# music_visualizer.net
KiCad netlist of a schematic drawn in EAGLE
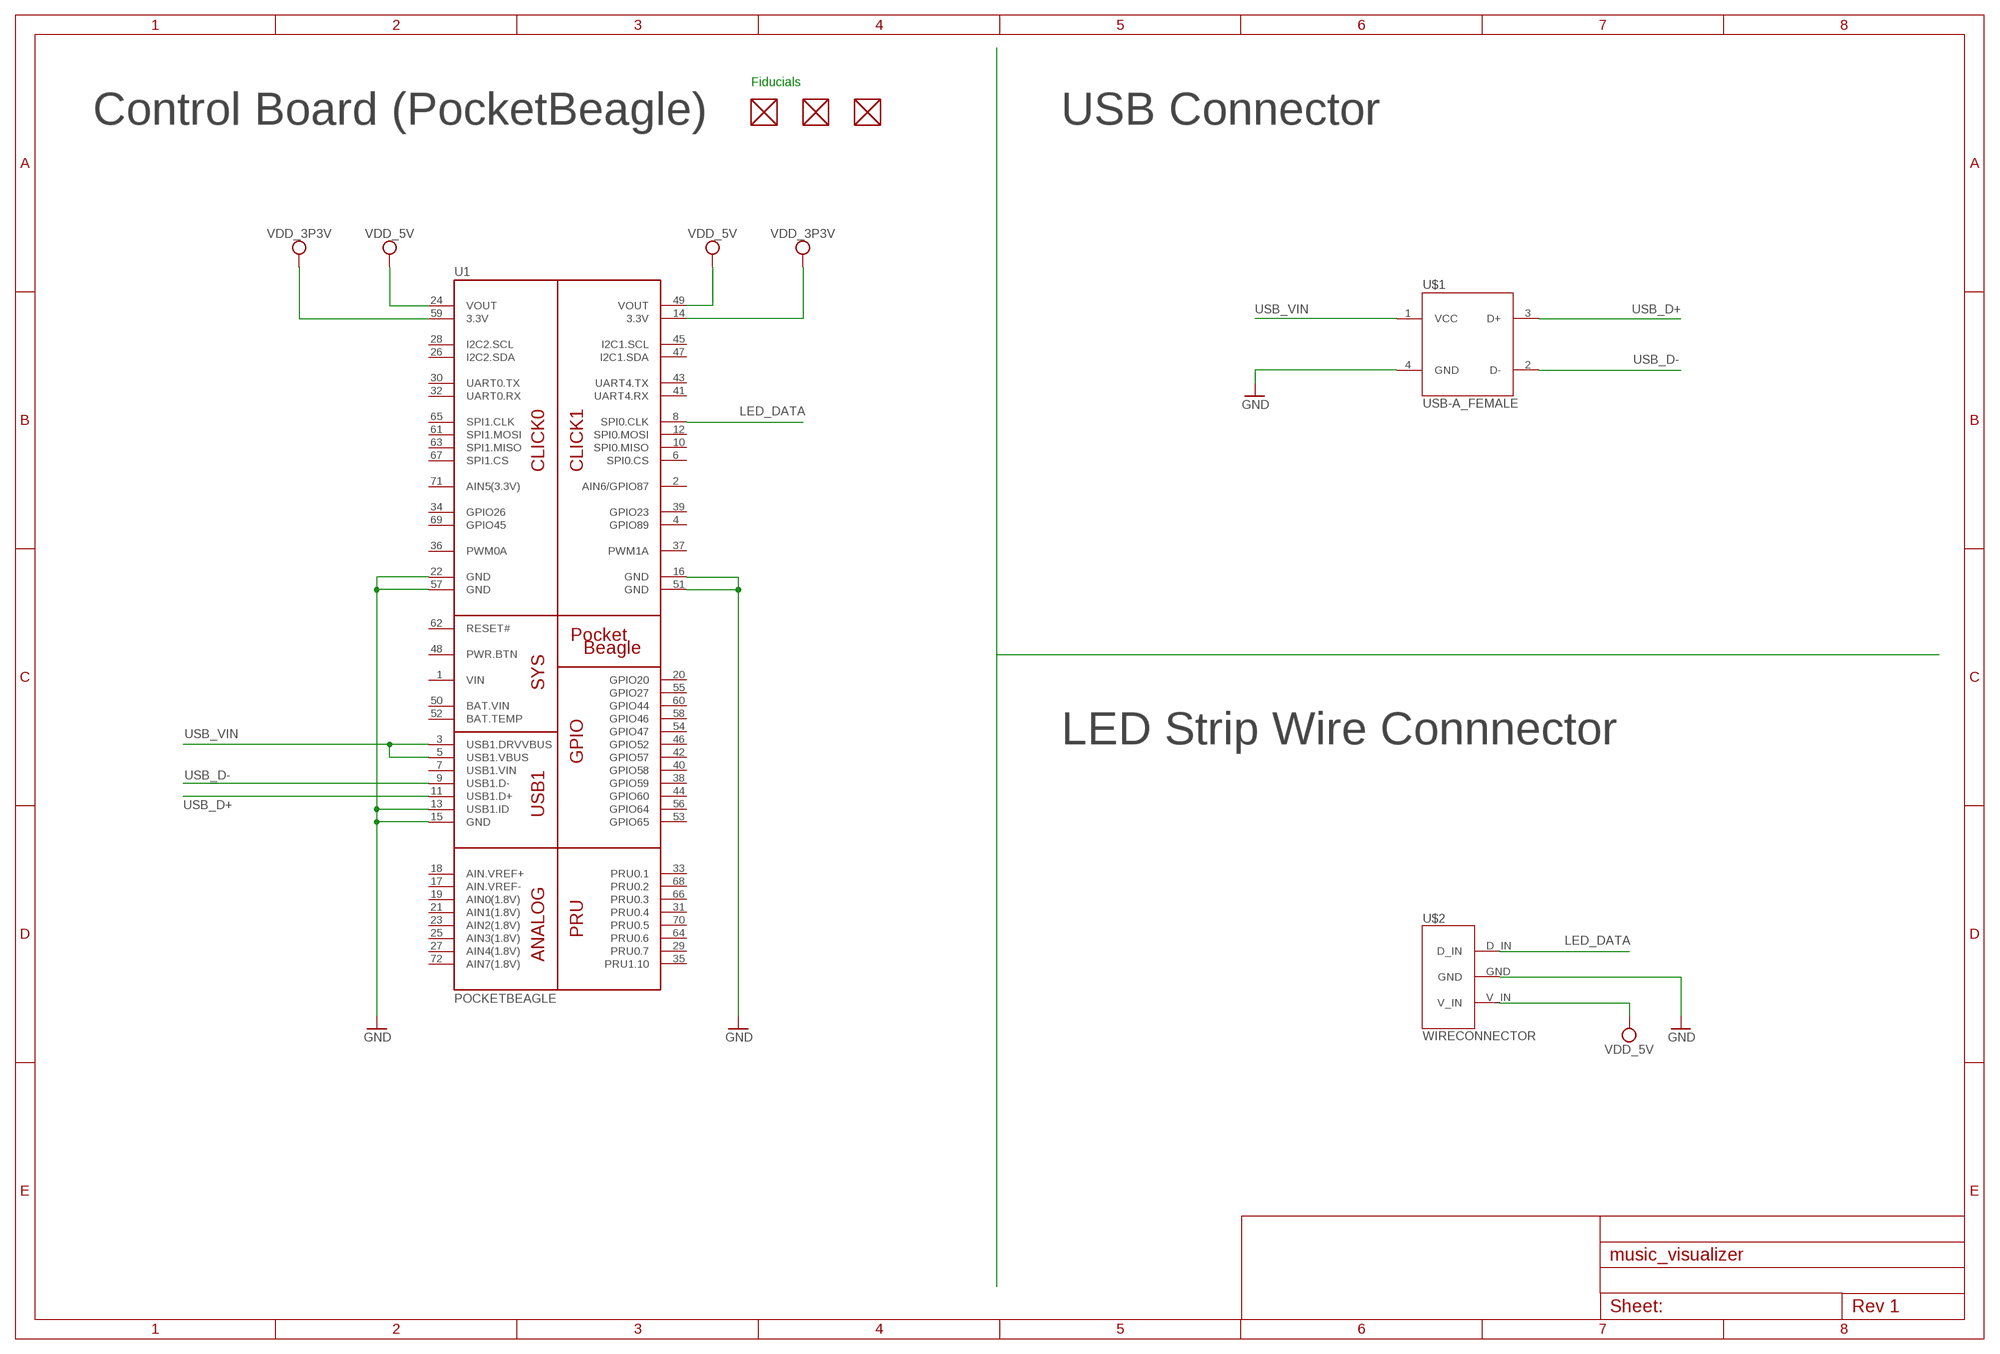
[diagram p0: schematic, sheet 1]

(export (version "E")
  (design (tool "Eeschema 10.0.6"))
  (components
    (comp (ref "FUD1")
      (value "FIDUCIAL")
      (footprint "eagle-import:FIDUCIAL_40MIL")
      (libsource (lib "eagle-import") (part "FIDUCIAL"))
    )
    (comp (ref "FUD2")
      (value "FIDUCIAL")
      (footprint "eagle-import:FIDUCIAL_40MIL")
      (libsource (lib "eagle-import") (part "FIDUCIAL"))
    )
    (comp (ref "FUD3")
      (value "FIDUCIAL")
      (footprint "eagle-import:FIDUCIAL_40MIL")
      (libsource (lib "eagle-import") (part "FIDUCIAL"))
    )
    (comp (ref "U$1")
      (value "USB-A_FEMALE")
      (footprint "eagle-import:USB-A_FEMALE")
      (libsource (lib "eagle-import") (part "USB-A_FEMALE"))
    )
    (comp (ref "U$2")
      (value "WIRECONNECTOR")
      (footprint "eagle-import:WIRECONNECTOR")
      (libsource (lib "eagle-import") (part "WIRECONNECTOR"))
    )
    (comp (ref "U1")
      (value "POCKETBEAGLE")
      (footprint "eagle-import:POCKETBEAGLE")
      (libsource (lib "eagle-import") (part "POCKETBEAGLE"))
    )
  )
  (nets
    (net (code "1") (name "/BAT.VIN") (class "Default")
      (node (ref "U1") (pin "50") (pinfunction "BAT.VIN_50") (pintype "power_in"))
    )
    (net (code "2") (name "/LED_DATA") (class "Default")
      (node (ref "U$2") (pin "D_IN") (pinfunction "D_IN_D_IN") (pintype "bidirectional"))
      (node (ref "U1") (pin "8") (pinfunction "SPI0.CLK_8") (pintype "bidirectional"))
    )
    (net (code "3") (name "/USB_D+") (class "Default")
      (node (ref "U$1") (pin "3") (pinfunction "D+_3") (pintype "bidirectional"))
      (node (ref "U1") (pin "11") (pinfunction "USB1.D+_11") (pintype "bidirectional"))
    )
    (net (code "4") (name "/USB_D-") (class "Default")
      (node (ref "U$1") (pin "2") (pinfunction "D-_2") (pintype "bidirectional"))
      (node (ref "U1") (pin "9") (pinfunction "USB1.D-_9") (pintype "bidirectional"))
    )
    (net (code "5") (name "/USB_VIN") (class "Default")
      (node (ref "U$1") (pin "1") (pinfunction "VCC_1") (pintype "bidirectional"))
      (node (ref "U1") (pin "3") (pinfunction "USB1.DRVVBUS_3") (pintype "bidirectional"))
      (node (ref "U1") (pin "5") (pinfunction "USB1.VBUS_5") (pintype "bidirectional"))
    )
    (net (code "6") (name "/VIN") (class "Default")
      (node (ref "U1") (pin "1") (pinfunction "VIN_1") (pintype "power_in"))
    )
    (net (code "7") (name "GND") (class "Default")
      (node (ref "U$1") (pin "4") (pinfunction "GND_4") (pintype "bidirectional"))
      (node (ref "U$2") (pin "GND") (pinfunction "GND_GND") (pintype "bidirectional"))
      (node (ref "U1") (pin "13") (pinfunction "USB1.ID_13") (pintype "bidirectional"))
      (node (ref "U1") (pin "15") (pinfunction "GND_15") (pintype "bidirectional"))
      (node (ref "U1") (pin "16") (pinfunction "GND_16") (pintype "power_in"))
      (node (ref "U1") (pin "22") (pinfunction "GND_22") (pintype "power_in"))
      (node (ref "U1") (pin "51") (pinfunction "GND_51") (pintype "power_in"))
      (node (ref "U1") (pin "57") (pinfunction "GND_57") (pintype "power_in"))
    )
    (net (code "8") (name "VDD_3P3V") (class "Default")
      (node (ref "U1") (pin "14") (pinfunction "3.3V_14") (pintype "power_in"))
      (node (ref "U1") (pin "59") (pinfunction "3.3V_59") (pintype "power_in"))
    )
    (net (code "9") (name "VDD_5V") (class "Default")
      (node (ref "U$2") (pin "V_IN") (pinfunction "V_IN_V_IN") (pintype "bidirectional"))
      (node (ref "U1") (pin "24") (pinfunction "VOUT_24") (pintype "power_in"))
      (node (ref "U1") (pin "49") (pinfunction "VOUT_49") (pintype "power_in"))
    )
    (net (code "10") (name "unconnected-(FUD1-PadP$1)") (class "Default")
      (node (ref "FUD1") (pin "P$1") (pinfunction "P$1_P$1") (pintype "no_connect"))
    )
    (net (code "11") (name "unconnected-(FUD2-PadP$1)") (class "Default")
      (node (ref "FUD2") (pin "P$1") (pinfunction "P$1_P$1") (pintype "no_connect"))
    )
    (net (code "12") (name "unconnected-(FUD3-PadP$1)") (class "Default")
      (node (ref "FUD3") (pin "P$1") (pinfunction "P$1_P$1") (pintype "no_connect"))
    )
    (net (code "13") (name "unconnected-(U1-AIN.VREF+-Pad18)") (class "Default")
      (node (ref "U1") (pin "18") (pinfunction "AIN.VREF+_18") (pintype "input"))
    )
    (net (code "14") (name "unconnected-(U1-AIN.VREF--Pad17)") (class "Default")
      (node (ref "U1") (pin "17") (pinfunction "AIN.VREF-_17") (pintype "input"))
    )
    (net (code "15") (name "unconnected-(U1-AIN0(1.8V)-Pad19)") (class "Default")
      (node (ref "U1") (pin "19") (pinfunction "AIN0(1.8V)_19") (pintype "input"))
    )
    (net (code "16") (name "unconnected-(U1-AIN1(1.8V)-Pad21)") (class "Default")
      (node (ref "U1") (pin "21") (pinfunction "AIN1(1.8V)_21") (pintype "input"))
    )
    (net (code "17") (name "unconnected-(U1-AIN2(1.8V)-Pad23)") (class "Default")
      (node (ref "U1") (pin "23") (pinfunction "AIN2(1.8V)_23") (pintype "input"))
    )
    (net (code "18") (name "unconnected-(U1-AIN3(1.8V)-Pad25)") (class "Default")
      (node (ref "U1") (pin "25") (pinfunction "AIN3(1.8V)_25") (pintype "input"))
    )
    (net (code "19") (name "unconnected-(U1-AIN4(1.8V)-Pad27)") (class "Default")
      (node (ref "U1") (pin "27") (pinfunction "AIN4(1.8V)_27") (pintype "input"))
    )
    (net (code "20") (name "unconnected-(U1-AIN5(3.3V)-Pad71)") (class "Default")
      (node (ref "U1") (pin "71") (pinfunction "AIN5(3.3V)_71") (pintype "bidirectional"))
    )
    (net (code "21") (name "unconnected-(U1-AIN6{slash}GPIO87-Pad2)") (class "Default")
      (node (ref "U1") (pin "2") (pinfunction "AIN6/GPIO87_2") (pintype "bidirectional"))
    )
    (net (code "22") (name "unconnected-(U1-AIN7(1.8V)-Pad72)") (class "Default")
      (node (ref "U1") (pin "72") (pinfunction "AIN7(1.8V)_72") (pintype "input"))
    )
    (net (code "23") (name "unconnected-(U1-BAT.TEMP-Pad52)") (class "Default")
      (node (ref "U1") (pin "52") (pinfunction "BAT.TEMP_52") (pintype "input"))
    )
    (net (code "24") (name "unconnected-(U1-GPIO20-Pad20)") (class "Default")
      (node (ref "U1") (pin "20") (pinfunction "GPIO20_20") (pintype "bidirectional"))
    )
    (net (code "25") (name "unconnected-(U1-GPIO23-Pad39)") (class "Default")
      (node (ref "U1") (pin "39") (pinfunction "GPIO23_39") (pintype "bidirectional"))
    )
    (net (code "26") (name "unconnected-(U1-GPIO26-Pad34)") (class "Default")
      (node (ref "U1") (pin "34") (pinfunction "GPIO26_34") (pintype "bidirectional"))
    )
    (net (code "27") (name "unconnected-(U1-GPIO27-Pad55)") (class "Default")
      (node (ref "U1") (pin "55") (pinfunction "GPIO27_55") (pintype "bidirectional"))
    )
    (net (code "28") (name "unconnected-(U1-GPIO44-Pad60)") (class "Default")
      (node (ref "U1") (pin "60") (pinfunction "GPIO44_60") (pintype "bidirectional"))
    )
    (net (code "29") (name "unconnected-(U1-GPIO45-Pad69)") (class "Default")
      (node (ref "U1") (pin "69") (pinfunction "GPIO45_69") (pintype "bidirectional"))
    )
    (net (code "30") (name "unconnected-(U1-GPIO46-Pad58)") (class "Default")
      (node (ref "U1") (pin "58") (pinfunction "GPIO46_58") (pintype "bidirectional"))
    )
    (net (code "31") (name "unconnected-(U1-GPIO47-Pad54)") (class "Default")
      (node (ref "U1") (pin "54") (pinfunction "GPIO47_54") (pintype "bidirectional"))
    )
    (net (code "32") (name "unconnected-(U1-GPIO52-Pad46)") (class "Default")
      (node (ref "U1") (pin "46") (pinfunction "GPIO52_46") (pintype "bidirectional"))
    )
    (net (code "33") (name "unconnected-(U1-GPIO57-Pad42)") (class "Default")
      (node (ref "U1") (pin "42") (pinfunction "GPIO57_42") (pintype "bidirectional"))
    )
    (net (code "34") (name "unconnected-(U1-GPIO58-Pad40)") (class "Default")
      (node (ref "U1") (pin "40") (pinfunction "GPIO58_40") (pintype "bidirectional"))
    )
    (net (code "35") (name "unconnected-(U1-GPIO59-Pad38)") (class "Default")
      (node (ref "U1") (pin "38") (pinfunction "GPIO59_38") (pintype "bidirectional"))
    )
    (net (code "36") (name "unconnected-(U1-GPIO60-Pad44)") (class "Default")
      (node (ref "U1") (pin "44") (pinfunction "GPIO60_44") (pintype "bidirectional"))
    )
    (net (code "37") (name "unconnected-(U1-GPIO64-Pad56)") (class "Default")
      (node (ref "U1") (pin "56") (pinfunction "GPIO64_56") (pintype "bidirectional"))
    )
    (net (code "38") (name "unconnected-(U1-GPIO65-Pad53)") (class "Default")
      (node (ref "U1") (pin "53") (pinfunction "GPIO65_53") (pintype "bidirectional"))
    )
    (net (code "39") (name "unconnected-(U1-GPIO89-Pad4)") (class "Default")
      (node (ref "U1") (pin "4") (pinfunction "GPIO89_4") (pintype "bidirectional"))
    )
    (net (code "40") (name "unconnected-(U1-I2C1.SCL-Pad45)") (class "Default")
      (node (ref "U1") (pin "45") (pinfunction "I2C1.SCL_45") (pintype "bidirectional"))
    )
    (net (code "41") (name "unconnected-(U1-I2C1.SDA-Pad47)") (class "Default")
      (node (ref "U1") (pin "47") (pinfunction "I2C1.SDA_47") (pintype "bidirectional"))
    )
    (net (code "42") (name "unconnected-(U1-I2C2.SCL-Pad28)") (class "Default")
      (node (ref "U1") (pin "28") (pinfunction "I2C2.SCL_28") (pintype "bidirectional"))
    )
    (net (code "43") (name "unconnected-(U1-I2C2.SDA-Pad26)") (class "Default")
      (node (ref "U1") (pin "26") (pinfunction "I2C2.SDA_26") (pintype "bidirectional"))
    )
    (net (code "44") (name "unconnected-(U1-PRU0.1-Pad33)") (class "Default")
      (node (ref "U1") (pin "33") (pinfunction "PRU0.1_33") (pintype "bidirectional"))
    )
    (net (code "45") (name "unconnected-(U1-PRU0.2-Pad68)") (class "Default")
      (node (ref "U1") (pin "68") (pinfunction "PRU0.2_68") (pintype "bidirectional"))
    )
    (net (code "46") (name "unconnected-(U1-PRU0.3-Pad66)") (class "Default")
      (node (ref "U1") (pin "66") (pinfunction "PRU0.3_66") (pintype "bidirectional"))
    )
    (net (code "47") (name "unconnected-(U1-PRU0.4-Pad31)") (class "Default")
      (node (ref "U1") (pin "31") (pinfunction "PRU0.4_31") (pintype "bidirectional"))
    )
    (net (code "48") (name "unconnected-(U1-PRU0.5-Pad70)") (class "Default")
      (node (ref "U1") (pin "70") (pinfunction "PRU0.5_70") (pintype "bidirectional"))
    )
    (net (code "49") (name "unconnected-(U1-PRU0.6-Pad64)") (class "Default")
      (node (ref "U1") (pin "64") (pinfunction "PRU0.6_64") (pintype "bidirectional"))
    )
    (net (code "50") (name "unconnected-(U1-PRU0.7-Pad29)") (class "Default")
      (node (ref "U1") (pin "29") (pinfunction "PRU0.7_29") (pintype "bidirectional"))
    )
    (net (code "51") (name "unconnected-(U1-PRU1.10-Pad35)") (class "Default")
      (node (ref "U1") (pin "35") (pinfunction "PRU1.10_35") (pintype "bidirectional"))
    )
    (net (code "52") (name "unconnected-(U1-PWM0A-Pad36)") (class "Default")
      (node (ref "U1") (pin "36") (pinfunction "PWM0A_36") (pintype "bidirectional"))
    )
    (net (code "53") (name "unconnected-(U1-PWM1A-Pad37)") (class "Default")
      (node (ref "U1") (pin "37") (pinfunction "PWM1A_37") (pintype "bidirectional"))
    )
    (net (code "54") (name "unconnected-(U1-PWR.BTN-Pad48)") (class "Default")
      (node (ref "U1") (pin "48") (pinfunction "PWR.BTN_48") (pintype "input"))
    )
    (net (code "55") (name "unconnected-(U1-RESET#-Pad62)") (class "Default")
      (node (ref "U1") (pin "62") (pinfunction "RESET#_62") (pintype "input"))
    )
    (net (code "56") (name "unconnected-(U1-SPI0.CS-Pad6)") (class "Default")
      (node (ref "U1") (pin "6") (pinfunction "SPI0.CS_6") (pintype "bidirectional"))
    )
    (net (code "57") (name "unconnected-(U1-SPI0.MISO-Pad10)") (class "Default")
      (node (ref "U1") (pin "10") (pinfunction "SPI0.MISO_10") (pintype "bidirectional"))
    )
    (net (code "58") (name "unconnected-(U1-SPI0.MOSI-Pad12)") (class "Default")
      (node (ref "U1") (pin "12") (pinfunction "SPI0.MOSI_12") (pintype "bidirectional"))
    )
    (net (code "59") (name "unconnected-(U1-SPI1.CLK-Pad65)") (class "Default")
      (node (ref "U1") (pin "65") (pinfunction "SPI1.CLK_65") (pintype "bidirectional"))
    )
    (net (code "60") (name "unconnected-(U1-SPI1.CS-Pad67)") (class "Default")
      (node (ref "U1") (pin "67") (pinfunction "SPI1.CS_67") (pintype "bidirectional"))
    )
    (net (code "61") (name "unconnected-(U1-SPI1.MISO-Pad63)") (class "Default")
      (node (ref "U1") (pin "63") (pinfunction "SPI1.MISO_63") (pintype "bidirectional"))
    )
    (net (code "62") (name "unconnected-(U1-SPI1.MOSI-Pad61)") (class "Default")
      (node (ref "U1") (pin "61") (pinfunction "SPI1.MOSI_61") (pintype "bidirectional"))
    )
    (net (code "63") (name "unconnected-(U1-UART0.RX-Pad32)") (class "Default")
      (node (ref "U1") (pin "32") (pinfunction "UART0.RX_32") (pintype "bidirectional"))
    )
    (net (code "64") (name "unconnected-(U1-UART0.TX-Pad30)") (class "Default")
      (node (ref "U1") (pin "30") (pinfunction "UART0.TX_30") (pintype "bidirectional"))
    )
    (net (code "65") (name "unconnected-(U1-UART4.RX-Pad41)") (class "Default")
      (node (ref "U1") (pin "41") (pinfunction "UART4.RX_41") (pintype "bidirectional"))
    )
    (net (code "66") (name "unconnected-(U1-UART4.TX-Pad43)") (class "Default")
      (node (ref "U1") (pin "43") (pinfunction "UART4.TX_43") (pintype "bidirectional"))
    )
    (net (code "67") (name "unconnected-(U1-USB1.VIN-Pad7)") (class "Default")
      (node (ref "U1") (pin "7") (pinfunction "USB1.VIN_7") (pintype "bidirectional"))
    )
  )
)
